# breakouts.net
KiCad netlist of a schematic drawn in EAGLE
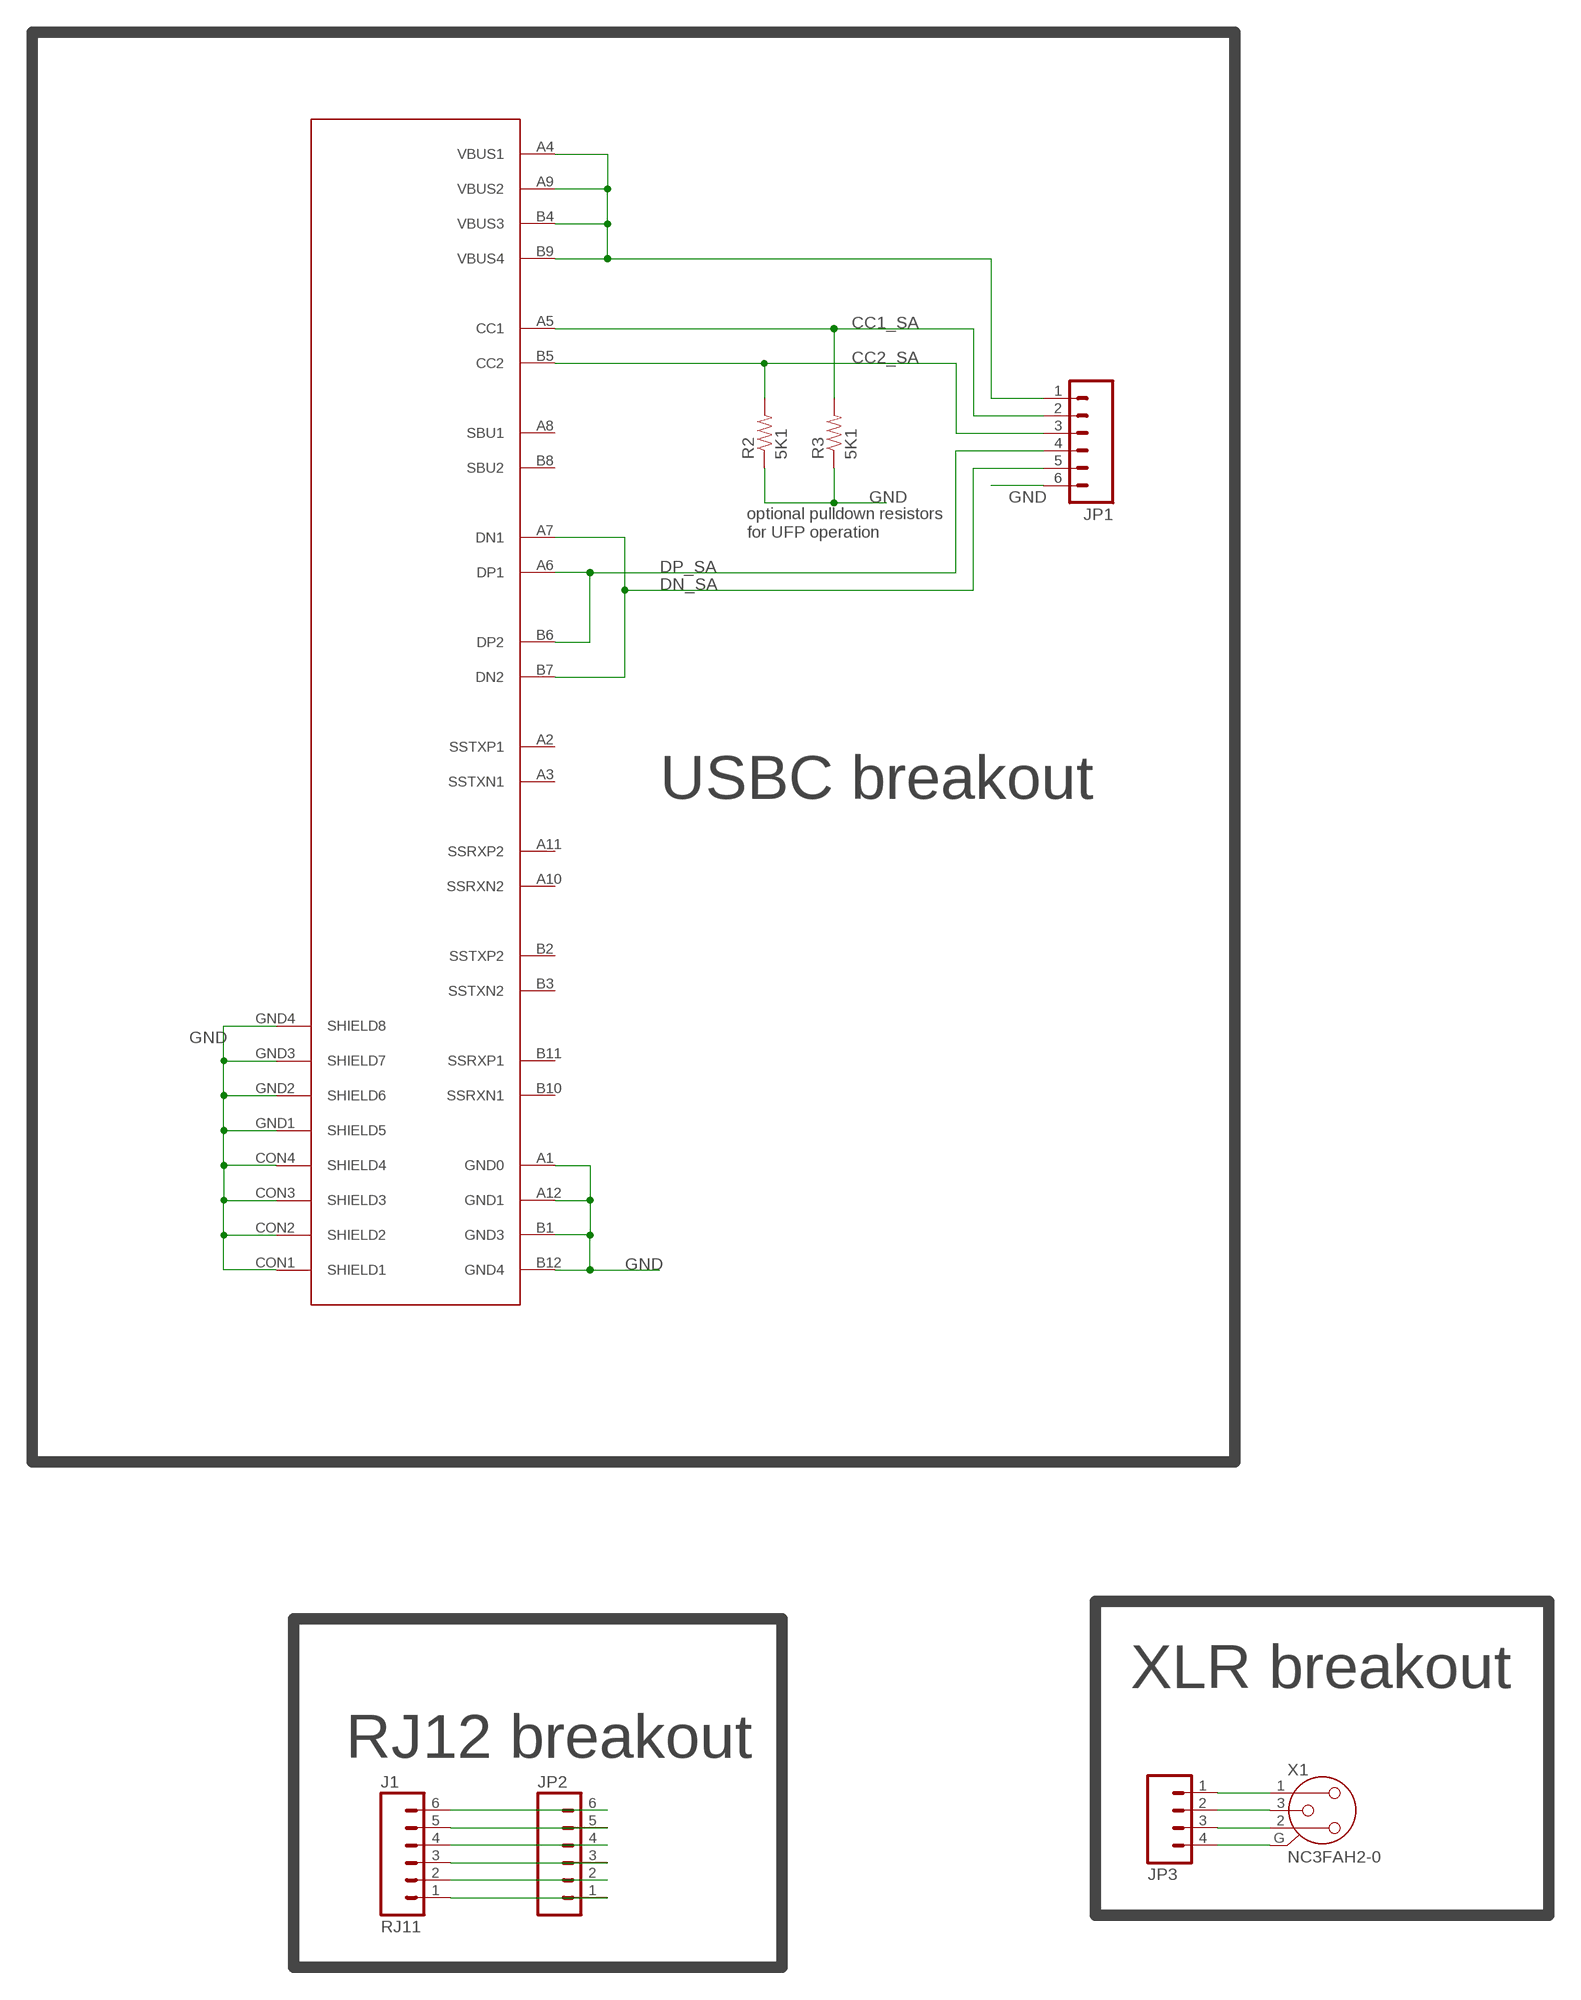
[diagram p0: schematic, sheet 1, part 1 of 2]
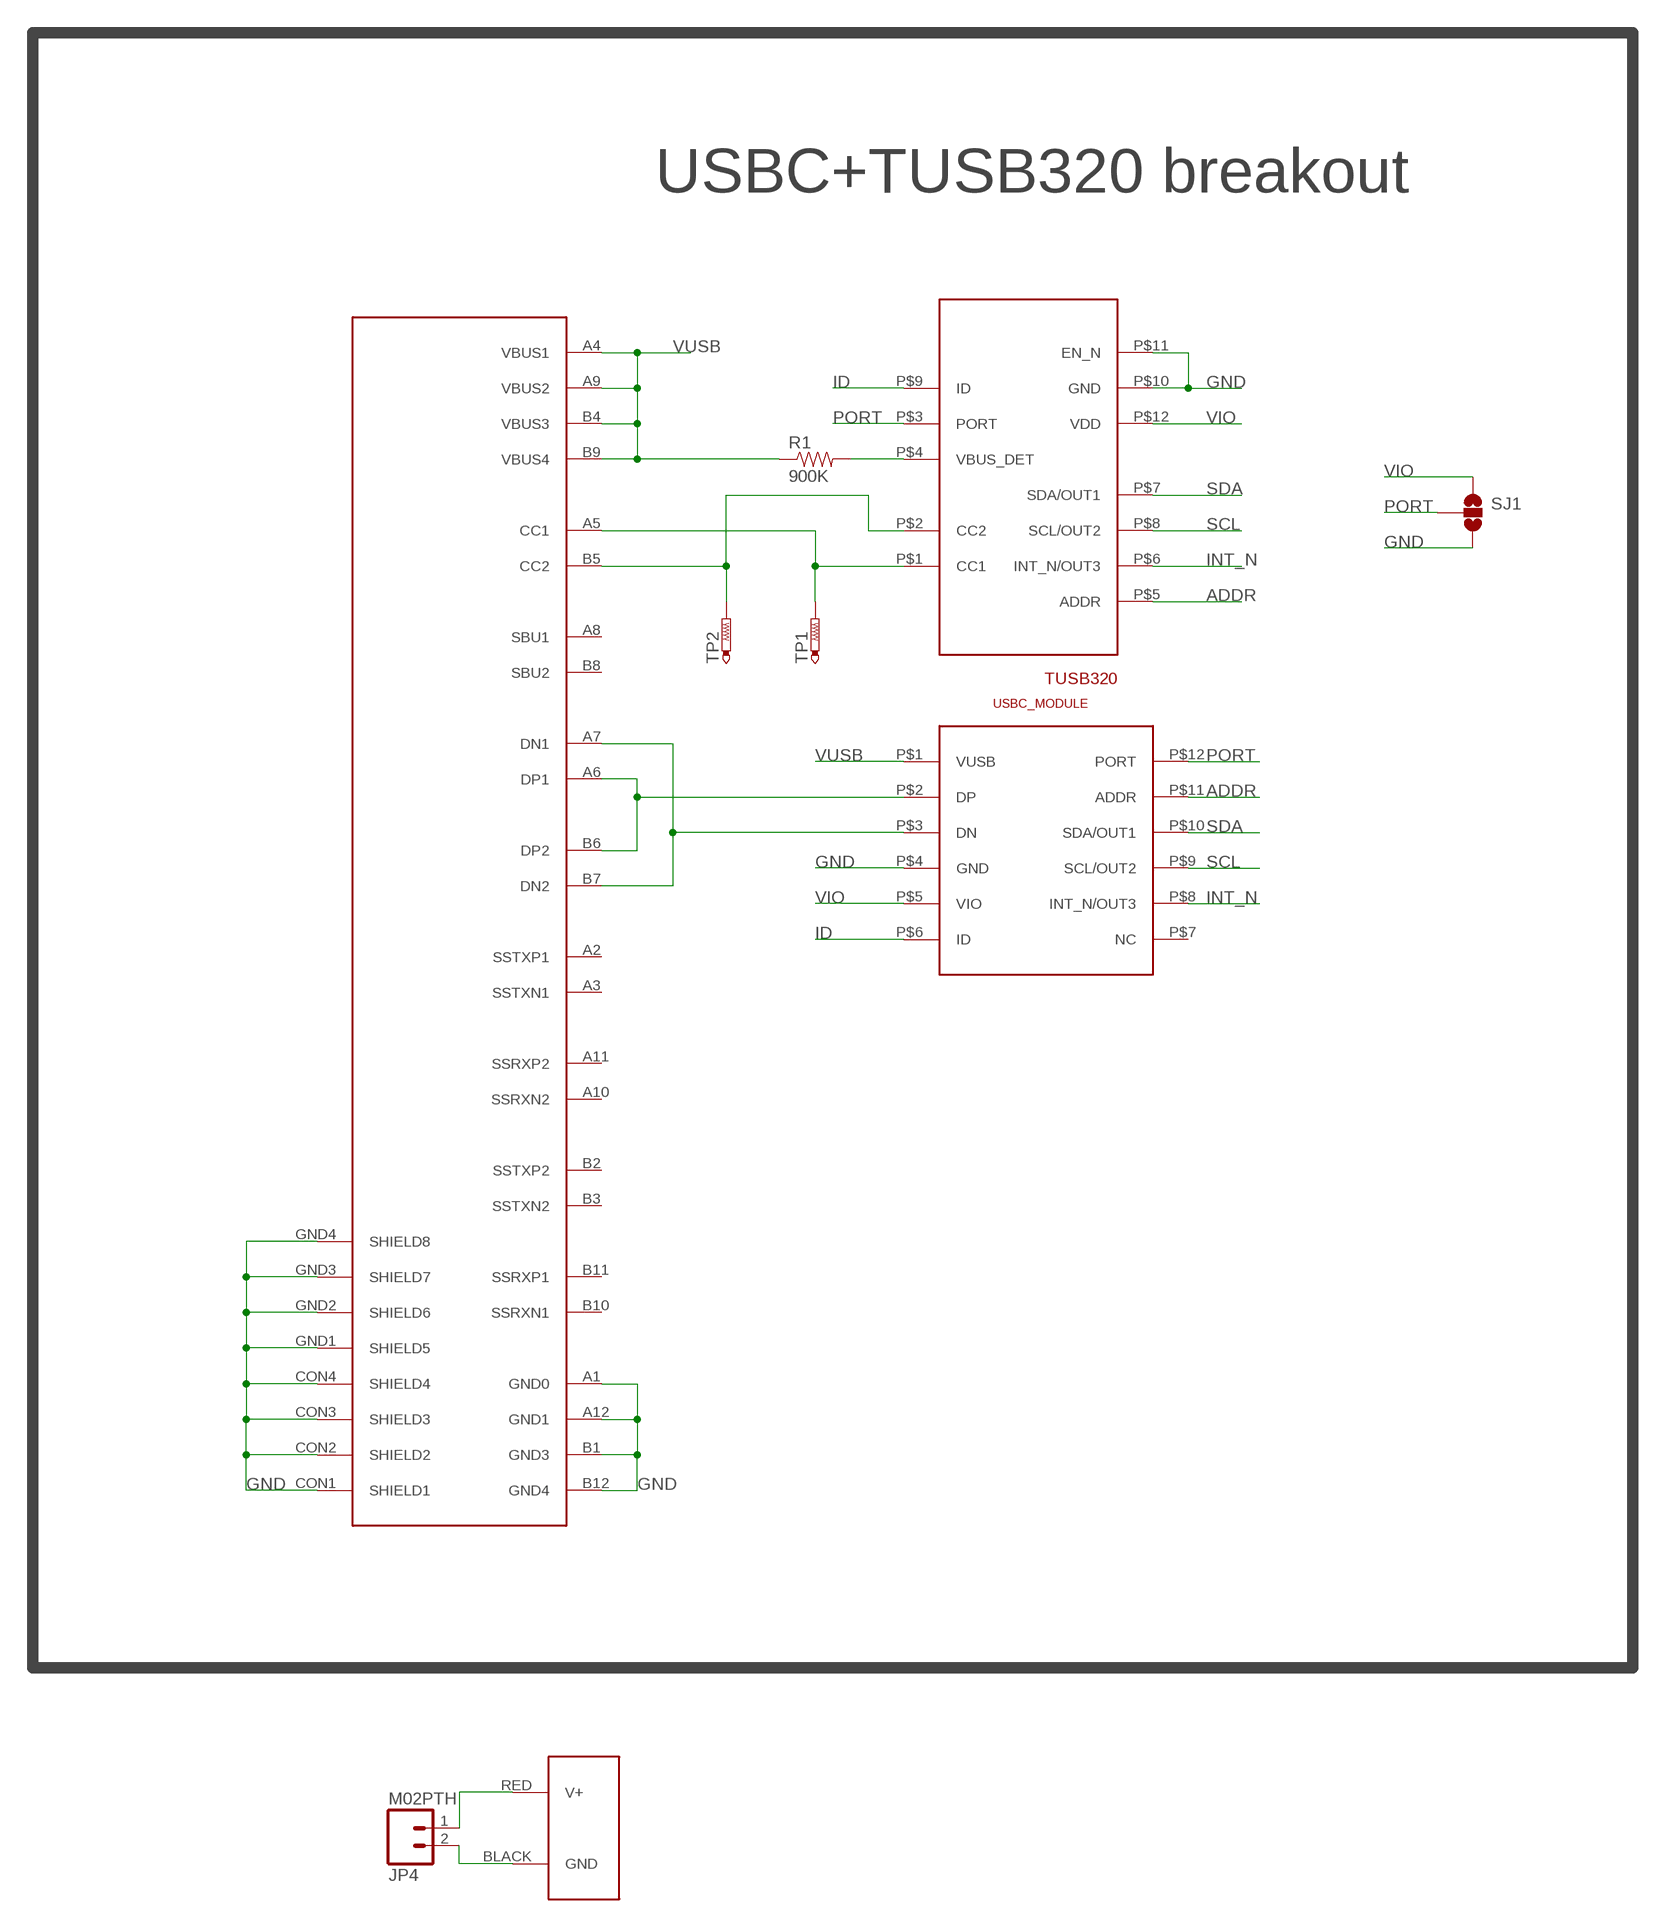
[diagram p1: schematic, sheet 1, part 2 of 2]

(export (version "E")
  (design (tool "Eeschema 10.0.6"))
  (components
    (comp (ref "CONN1")
      (value "USB-C_WURTH_632723X00011USB-C")
      (footprint "eagle-import:USB-C_WURTH_632723X00011")
      (libsource (lib "eagle-import") (part "USB-C_WURTH_632723X00011USB-C"))
    )
    (comp (ref "CONN2")
      (value "USB-C_WURTH_632723X00011USB-C")
      (footprint "eagle-import:USB-C_WURTH_632723X00011")
      (libsource (lib "eagle-import") (part "USB-C_WURTH_632723X00011USB-C"))
    )
    (comp (ref "J1")
      (value "RJ11")
      (footprint "eagle-import:RJ11-6")
      (libsource (lib "eagle-import") (part "RJ11-6PTH"))
    )
    (comp (ref "J2")
      (value "POWERPOLE_POWER25A")
      (footprint "eagle-import:POWERPOLE_PAIR_25A")
      (libsource (lib "eagle-import") (part "POWERPOLE_POWER25A"))
    )
    (comp (ref "JP1")
      (value "M06SIP")
      (footprint "eagle-import:1X06")
      (libsource (lib "eagle-import") (part "M06SIP"))
    )
    (comp (ref "JP2")
      (value "M06SIP")
      (footprint "eagle-import:1X06")
      (libsource (lib "eagle-import") (part "M06SIP"))
    )
    (comp (ref "JP3")
      (value "M04PTH")
      (footprint "eagle-import:1X04")
      (libsource (lib "eagle-import") (part "M04PTH"))
    )
    (comp (ref "JP4")
      (value "M02PTH")
      (footprint "eagle-import:1X02")
      (libsource (lib "eagle-import") (part "M02PTH"))
    )
    (comp (ref "R1")
      (value "900K")
      (footprint "eagle-import:0603-RES")
      (libsource (lib "eagle-import") (part "RESISTOR0603-RES"))
    )
    (comp (ref "R2")
      (value "5K1")
      (footprint "eagle-import:0603-RES")
      (libsource (lib "eagle-import") (part "RESISTOR0603-RES"))
    )
    (comp (ref "R3")
      (value "5K1")
      (footprint "eagle-import:0603-RES")
      (libsource (lib "eagle-import") (part "RESISTOR0603-RES"))
    )
    (comp (ref "SJ1")
      (value "SOLDERJUMPER_2WAYS")
      (footprint "eagle-import:SJ_3")
      (libsource (lib "eagle-import") (part "SOLDERJUMPER_2WAYS"))
    )
    (comp (ref "TP1")
      (value "PTR1TP10R")
      (footprint "eagle-import:TP10R")
      (libsource (lib "eagle-import") (part "PTR1TP10R"))
    )
    (comp (ref "TP2")
      (value "PTR1TP10R")
      (footprint "eagle-import:TP10R")
      (libsource (lib "eagle-import") (part "PTR1TP10R"))
    )
    (comp (ref "U$1")
      (value "TUSB320XQFN")
      (footprint "eagle-import:X2QFN")
      (libsource (lib "eagle-import") (part "TUSB320XQFN"))
    )
    (comp (ref "U$2")
      (value "USBC_BREAKOUTPDIP")
      (footprint "eagle-import:DIP12_6WIDE")
      (libsource (lib "eagle-import") (part "USBC_BREAKOUTPDIP"))
    )
    (comp (ref "X1")
      (value "NC3FAH2-0")
      (footprint "eagle-import:NC3FAH2-0")
      (fields (field (name "MPN") "NC3FAH-2-0"))
      (libsource (lib "eagle-import") (part "NC3FAH2-0"))
    )
  )
  (nets
    (net (code "1") (name "/ADDR") (class "Default")
      (node (ref "U$1") (pin "P$5") (pinfunction "ADDR_P$5") (pintype "bidirectional"))
      (node (ref "U$2") (pin "P$11") (pinfunction "ADDR_P$11") (pintype "bidirectional"))
    )
    (net (code "2") (name "/CC1_SA") (class "Default")
      (node (ref "CONN2") (pin "A5") (pinfunction "CC1_A5") (pintype "bidirectional"))
      (node (ref "JP1") (pin "2") (pinfunction "2_2") (pintype "passive"))
      (node (ref "R3") (pin "2") (pinfunction "2_2") (pintype "passive"))
    )
    (net (code "3") (name "/CC2_SA") (class "Default")
      (node (ref "CONN2") (pin "B5") (pinfunction "CC2_B5") (pintype "bidirectional"))
      (node (ref "JP1") (pin "3") (pinfunction "3_3") (pintype "passive"))
      (node (ref "R2") (pin "2") (pinfunction "2_2") (pintype "passive"))
    )
    (net (code "4") (name "/DN_SA") (class "Default")
      (node (ref "CONN2") (pin "A7") (pinfunction "DN1_A7") (pintype "bidirectional"))
      (node (ref "CONN2") (pin "B7") (pinfunction "DN2_B7") (pintype "bidirectional"))
      (node (ref "JP1") (pin "5") (pinfunction "5_5") (pintype "passive"))
    )
    (net (code "5") (name "/DP_SA") (class "Default")
      (node (ref "CONN2") (pin "A6") (pinfunction "DP1_A6") (pintype "bidirectional"))
      (node (ref "CONN2") (pin "B6") (pinfunction "DP2_B6") (pintype "bidirectional"))
      (node (ref "JP1") (pin "4") (pinfunction "4_4") (pintype "passive"))
    )
    (net (code "6") (name "/GND") (class "Default")
      (node (ref "CONN1") (pin "A1") (pinfunction "GND0_A1") (pintype "bidirectional"))
      (node (ref "CONN1") (pin "A12") (pinfunction "GND1_A12") (pintype "bidirectional"))
      (node (ref "CONN1") (pin "B1") (pinfunction "GND3_B1") (pintype "bidirectional"))
      (node (ref "CONN1") (pin "B12") (pinfunction "GND4_B12") (pintype "bidirectional"))
      (node (ref "CONN1") (pin "CON1") (pinfunction "SHIELD1_CON1") (pintype "bidirectional"))
      (node (ref "CONN1") (pin "CON2") (pinfunction "SHIELD2_CON2") (pintype "bidirectional"))
      (node (ref "CONN1") (pin "CON3") (pinfunction "SHIELD3_CON3") (pintype "bidirectional"))
      (node (ref "CONN1") (pin "CON4") (pinfunction "SHIELD4_CON4") (pintype "bidirectional"))
      (node (ref "CONN1") (pin "GND1") (pinfunction "SHIELD5_GND1") (pintype "bidirectional"))
      (node (ref "CONN1") (pin "GND2") (pinfunction "SHIELD6_GND2") (pintype "bidirectional"))
      (node (ref "CONN1") (pin "GND3") (pinfunction "SHIELD7_GND3") (pintype "bidirectional"))
      (node (ref "CONN1") (pin "GND4") (pinfunction "SHIELD8_GND4") (pintype "bidirectional"))
      (node (ref "CONN2") (pin "A1") (pinfunction "GND0_A1") (pintype "bidirectional"))
      (node (ref "CONN2") (pin "A12") (pinfunction "GND1_A12") (pintype "bidirectional"))
      (node (ref "CONN2") (pin "B1") (pinfunction "GND3_B1") (pintype "bidirectional"))
      (node (ref "CONN2") (pin "B12") (pinfunction "GND4_B12") (pintype "bidirectional"))
      (node (ref "CONN2") (pin "CON1") (pinfunction "SHIELD1_CON1") (pintype "bidirectional"))
      (node (ref "CONN2") (pin "CON2") (pinfunction "SHIELD2_CON2") (pintype "bidirectional"))
      (node (ref "CONN2") (pin "CON3") (pinfunction "SHIELD3_CON3") (pintype "bidirectional"))
      (node (ref "CONN2") (pin "CON4") (pinfunction "SHIELD4_CON4") (pintype "bidirectional"))
      (node (ref "CONN2") (pin "GND1") (pinfunction "SHIELD5_GND1") (pintype "bidirectional"))
      (node (ref "CONN2") (pin "GND2") (pinfunction "SHIELD6_GND2") (pintype "bidirectional"))
      (node (ref "CONN2") (pin "GND3") (pinfunction "SHIELD7_GND3") (pintype "bidirectional"))
      (node (ref "CONN2") (pin "GND4") (pinfunction "SHIELD8_GND4") (pintype "bidirectional"))
      (node (ref "JP1") (pin "6") (pinfunction "6_6") (pintype "passive"))
      (node (ref "R2") (pin "1") (pinfunction "1_1") (pintype "passive"))
      (node (ref "R3") (pin "1") (pinfunction "1_1") (pintype "passive"))
      (node (ref "SJ1") (pin "3") (pinfunction "3_3") (pintype "passive"))
      (node (ref "U$1") (pin "P$10") (pinfunction "GND_P$10") (pintype "bidirectional"))
      (node (ref "U$1") (pin "P$11") (pinfunction "EN_N_P$11") (pintype "bidirectional"))
      (node (ref "U$2") (pin "P$4") (pinfunction "GND_P$4") (pintype "bidirectional"))
    )
    (net (code "7") (name "/ID") (class "Default")
      (node (ref "U$1") (pin "P$9") (pinfunction "ID_P$9") (pintype "bidirectional"))
      (node (ref "U$2") (pin "P$6") (pinfunction "ID_P$6") (pintype "bidirectional"))
    )
    (net (code "8") (name "/INT_N") (class "Default")
      (node (ref "U$1") (pin "P$6") (pinfunction "INT_N/OUT3_P$6") (pintype "bidirectional"))
      (node (ref "U$2") (pin "P$8") (pinfunction "INT_N/OUT3_P$8") (pintype "bidirectional"))
    )
    (net (code "9") (name "/PORT") (class "Default")
      (node (ref "SJ1") (pin "2") (pinfunction "2_2") (pintype "passive"))
      (node (ref "U$1") (pin "P$3") (pinfunction "PORT_P$3") (pintype "bidirectional"))
      (node (ref "U$2") (pin "P$12") (pinfunction "PORT_P$12") (pintype "bidirectional"))
    )
    (net (code "10") (name "/SCL") (class "Default")
      (node (ref "U$1") (pin "P$8") (pinfunction "SCL/OUT2_P$8") (pintype "bidirectional"))
      (node (ref "U$2") (pin "P$9") (pinfunction "SCL/OUT2_P$9") (pintype "bidirectional"))
    )
    (net (code "11") (name "/SDA") (class "Default")
      (node (ref "U$1") (pin "P$7") (pinfunction "SDA/OUT1_P$7") (pintype "bidirectional"))
      (node (ref "U$2") (pin "P$10") (pinfunction "SDA/OUT1_P$10") (pintype "bidirectional"))
    )
    (net (code "12") (name "/VIO") (class "Default")
      (node (ref "SJ1") (pin "1") (pinfunction "1_1") (pintype "passive"))
      (node (ref "U$1") (pin "P$12") (pinfunction "VDD_P$12") (pintype "bidirectional"))
      (node (ref "U$2") (pin "P$5") (pinfunction "VIO_P$5") (pintype "bidirectional"))
    )
    (net (code "13") (name "/VUSB") (class "Default")
      (node (ref "CONN1") (pin "A4") (pinfunction "VBUS1_A4") (pintype "bidirectional"))
      (node (ref "CONN1") (pin "A9") (pinfunction "VBUS2_A9") (pintype "bidirectional"))
      (node (ref "CONN1") (pin "B4") (pinfunction "VBUS3_B4") (pintype "bidirectional"))
      (node (ref "CONN1") (pin "B9") (pinfunction "VBUS4_B9") (pintype "bidirectional"))
      (node (ref "R1") (pin "1") (pinfunction "1_1") (pintype "passive"))
      (node (ref "U$2") (pin "P$1") (pinfunction "VUSB_P$1") (pintype "bidirectional"))
    )
    (net (code "14") (name "Net-(CONN1-CC1)") (class "Default")
      (node (ref "CONN1") (pin "A5") (pinfunction "CC1_A5") (pintype "bidirectional"))
      (node (ref "TP1") (pin "TP") (pinfunction "TP_TP") (pintype "input"))
      (node (ref "U$1") (pin "P$1") (pinfunction "CC1_P$1") (pintype "bidirectional"))
    )
    (net (code "15") (name "Net-(CONN1-CC2)") (class "Default")
      (node (ref "CONN1") (pin "B5") (pinfunction "CC2_B5") (pintype "bidirectional"))
      (node (ref "TP2") (pin "TP") (pinfunction "TP_TP") (pintype "input"))
      (node (ref "U$1") (pin "P$2") (pinfunction "CC2_P$2") (pintype "bidirectional"))
    )
    (net (code "16") (name "Net-(CONN1-DN1)") (class "Default")
      (node (ref "CONN1") (pin "A7") (pinfunction "DN1_A7") (pintype "bidirectional"))
      (node (ref "CONN1") (pin "B7") (pinfunction "DN2_B7") (pintype "bidirectional"))
      (node (ref "U$2") (pin "P$3") (pinfunction "DN_P$3") (pintype "bidirectional"))
    )
    (net (code "17") (name "Net-(CONN1-DP1)") (class "Default")
      (node (ref "CONN1") (pin "A6") (pinfunction "DP1_A6") (pintype "bidirectional"))
      (node (ref "CONN1") (pin "B6") (pinfunction "DP2_B6") (pintype "bidirectional"))
      (node (ref "U$2") (pin "P$2") (pinfunction "DP_P$2") (pintype "bidirectional"))
    )
    (net (code "18") (name "Net-(CONN2-VBUS1)") (class "Default")
      (node (ref "CONN2") (pin "A4") (pinfunction "VBUS1_A4") (pintype "bidirectional"))
      (node (ref "CONN2") (pin "A9") (pinfunction "VBUS2_A9") (pintype "bidirectional"))
      (node (ref "CONN2") (pin "B4") (pinfunction "VBUS3_B4") (pintype "bidirectional"))
      (node (ref "CONN2") (pin "B9") (pinfunction "VBUS4_B9") (pintype "bidirectional"))
      (node (ref "JP1") (pin "1") (pinfunction "1_1") (pintype "passive"))
    )
    (net (code "19") (name "Net-(J1-Pad1)") (class "Default")
      (node (ref "J1") (pin "1") (pinfunction "1_1") (pintype "passive"))
      (node (ref "JP2") (pin "1") (pinfunction "1_1") (pintype "passive"))
    )
    (net (code "20") (name "Net-(J1-Pad2)") (class "Default")
      (node (ref "J1") (pin "2") (pinfunction "2_2") (pintype "passive"))
      (node (ref "JP2") (pin "2") (pinfunction "2_2") (pintype "passive"))
    )
    (net (code "21") (name "Net-(J1-Pad3)") (class "Default")
      (node (ref "J1") (pin "3") (pinfunction "3_3") (pintype "passive"))
      (node (ref "JP2") (pin "3") (pinfunction "3_3") (pintype "passive"))
    )
    (net (code "22") (name "Net-(J1-Pad4)") (class "Default")
      (node (ref "J1") (pin "4") (pinfunction "4_4") (pintype "passive"))
      (node (ref "JP2") (pin "4") (pinfunction "4_4") (pintype "passive"))
    )
    (net (code "23") (name "Net-(J1-Pad5)") (class "Default")
      (node (ref "J1") (pin "5") (pinfunction "5_5") (pintype "passive"))
      (node (ref "JP2") (pin "5") (pinfunction "5_5") (pintype "passive"))
    )
    (net (code "24") (name "Net-(J1-Pad6)") (class "Default")
      (node (ref "J1") (pin "6") (pinfunction "6_6") (pintype "passive"))
      (node (ref "JP2") (pin "6") (pinfunction "6_6") (pintype "passive"))
    )
    (net (code "25") (name "Net-(J2-GND)") (class "Default")
      (node (ref "J2") (pin "BLACK") (pinfunction "GND_BLACK") (pintype "power_in"))
      (node (ref "JP4") (pin "2") (pinfunction "2_2") (pintype "passive"))
    )
    (net (code "26") (name "Net-(J2-V+)") (class "Default")
      (node (ref "J2") (pin "RED") (pinfunction "V+_RED") (pintype "power_in"))
      (node (ref "JP4") (pin "1") (pinfunction "1_1") (pintype "passive"))
    )
    (net (code "27") (name "Net-(JP3-Pad1)") (class "Default")
      (node (ref "JP3") (pin "1") (pinfunction "1_1") (pintype "passive"))
      (node (ref "X1") (pin "1") (pinfunction "1_1") (pintype "passive"))
    )
    (net (code "28") (name "Net-(JP3-Pad2)") (class "Default")
      (node (ref "JP3") (pin "2") (pinfunction "2_2") (pintype "passive"))
      (node (ref "X1") (pin "3") (pinfunction "3_3") (pintype "passive"))
    )
    (net (code "29") (name "Net-(JP3-Pad3)") (class "Default")
      (node (ref "JP3") (pin "3") (pinfunction "3_3") (pintype "passive"))
      (node (ref "X1") (pin "2") (pinfunction "2_2") (pintype "passive"))
    )
    (net (code "30") (name "Net-(JP3-Pad4)") (class "Default")
      (node (ref "JP3") (pin "4") (pinfunction "4_4") (pintype "passive"))
      (node (ref "X1") (pin "G") (pinfunction "G_G") (pintype "passive"))
    )
    (net (code "31") (name "Net-(U$1-VBUS_DET)") (class "Default")
      (node (ref "R1") (pin "2") (pinfunction "2_2") (pintype "passive"))
      (node (ref "U$1") (pin "P$4") (pinfunction "VBUS_DET_P$4") (pintype "bidirectional"))
    )
    (net (code "32") (name "unconnected-(CONN1-SBU1-PadA8)") (class "Default")
      (node (ref "CONN1") (pin "A8") (pinfunction "SBU1_A8") (pintype "bidirectional"))
    )
    (net (code "33") (name "unconnected-(CONN1-SBU2-PadB8)") (class "Default")
      (node (ref "CONN1") (pin "B8") (pinfunction "SBU2_B8") (pintype "bidirectional"))
    )
    (net (code "34") (name "unconnected-(CONN1-SSRXN1-PadB10)") (class "Default")
      (node (ref "CONN1") (pin "B10") (pinfunction "SSRXN1_B10") (pintype "bidirectional"))
    )
    (net (code "35") (name "unconnected-(CONN1-SSRXN2-PadA10)") (class "Default")
      (node (ref "CONN1") (pin "A10") (pinfunction "SSRXN2_A10") (pintype "bidirectional"))
    )
    (net (code "36") (name "unconnected-(CONN1-SSRXP1-PadB11)") (class "Default")
      (node (ref "CONN1") (pin "B11") (pinfunction "SSRXP1_B11") (pintype "bidirectional"))
    )
    (net (code "37") (name "unconnected-(CONN1-SSRXP2-PadA11)") (class "Default")
      (node (ref "CONN1") (pin "A11") (pinfunction "SSRXP2_A11") (pintype "bidirectional"))
    )
    (net (code "38") (name "unconnected-(CONN1-SSTXN1-PadA3)") (class "Default")
      (node (ref "CONN1") (pin "A3") (pinfunction "SSTXN1_A3") (pintype "bidirectional"))
    )
    (net (code "39") (name "unconnected-(CONN1-SSTXN2-PadB3)") (class "Default")
      (node (ref "CONN1") (pin "B3") (pinfunction "SSTXN2_B3") (pintype "bidirectional"))
    )
    (net (code "40") (name "unconnected-(CONN1-SSTXP1-PadA2)") (class "Default")
      (node (ref "CONN1") (pin "A2") (pinfunction "SSTXP1_A2") (pintype "bidirectional"))
    )
    (net (code "41") (name "unconnected-(CONN1-SSTXP2-PadB2)") (class "Default")
      (node (ref "CONN1") (pin "B2") (pinfunction "SSTXP2_B2") (pintype "bidirectional"))
    )
    (net (code "42") (name "unconnected-(CONN2-SBU1-PadA8)") (class "Default")
      (node (ref "CONN2") (pin "A8") (pinfunction "SBU1_A8") (pintype "bidirectional"))
    )
    (net (code "43") (name "unconnected-(CONN2-SBU2-PadB8)") (class "Default")
      (node (ref "CONN2") (pin "B8") (pinfunction "SBU2_B8") (pintype "bidirectional"))
    )
    (net (code "44") (name "unconnected-(CONN2-SSRXN1-PadB10)") (class "Default")
      (node (ref "CONN2") (pin "B10") (pinfunction "SSRXN1_B10") (pintype "bidirectional"))
    )
    (net (code "45") (name "unconnected-(CONN2-SSRXN2-PadA10)") (class "Default")
      (node (ref "CONN2") (pin "A10") (pinfunction "SSRXN2_A10") (pintype "bidirectional"))
    )
    (net (code "46") (name "unconnected-(CONN2-SSRXP1-PadB11)") (class "Default")
      (node (ref "CONN2") (pin "B11") (pinfunction "SSRXP1_B11") (pintype "bidirectional"))
    )
    (net (code "47") (name "unconnected-(CONN2-SSRXP2-PadA11)") (class "Default")
      (node (ref "CONN2") (pin "A11") (pinfunction "SSRXP2_A11") (pintype "bidirectional"))
    )
    (net (code "48") (name "unconnected-(CONN2-SSTXN1-PadA3)") (class "Default")
      (node (ref "CONN2") (pin "A3") (pinfunction "SSTXN1_A3") (pintype "bidirectional"))
    )
    (net (code "49") (name "unconnected-(CONN2-SSTXN2-PadB3)") (class "Default")
      (node (ref "CONN2") (pin "B3") (pinfunction "SSTXN2_B3") (pintype "bidirectional"))
    )
    (net (code "50") (name "unconnected-(CONN2-SSTXP1-PadA2)") (class "Default")
      (node (ref "CONN2") (pin "A2") (pinfunction "SSTXP1_A2") (pintype "bidirectional"))
    )
    (net (code "51") (name "unconnected-(CONN2-SSTXP2-PadB2)") (class "Default")
      (node (ref "CONN2") (pin "B2") (pinfunction "SSTXP2_B2") (pintype "bidirectional"))
    )
    (net (code "52") (name "unconnected-(U$2-NC-PadP$7)") (class "Default")
      (node (ref "U$2") (pin "P$7") (pinfunction "NC_P$7") (pintype "bidirectional"))
    )
  )
)
